# Sheet1.net
KiCad netlist of a schematic drawn in Altium Designer
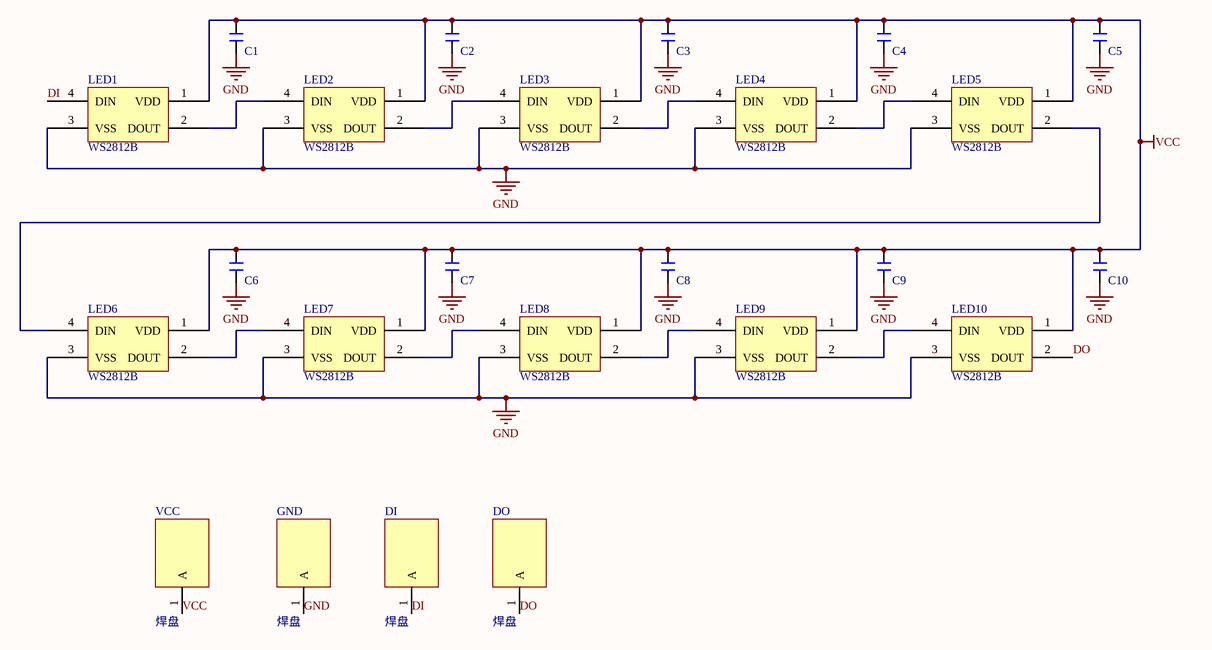
[diagram p0: Sheet1.SchDoc]

(export (version "E")
  (design (tool "Eeschema 10.0.6"))
  (components
    (comp (ref "C1")
      (value "104")
      (footprint "C 0805_M")
      (description "无极性贴片电容")
      (fields (field (name "版权归属") "源创客"))
      (libsource (lib "3.1   - 电阻-电容-电感") (part "C"))
    )
    (comp (ref "C2")
      (value "104")
      (footprint "C 0805_M")
      (description "无极性贴片电容")
      (fields (field (name "版权归属") "源创客"))
      (libsource (lib "3.1   - 电阻-电容-电感") (part "C"))
    )
    (comp (ref "C3")
      (value "104")
      (footprint "C 0805_M")
      (description "无极性贴片电容")
      (fields (field (name "版权归属") "源创客"))
      (libsource (lib "3.1   - 电阻-电容-电感") (part "C"))
    )
    (comp (ref "C4")
      (value "104")
      (footprint "C 0805_M")
      (description "无极性贴片电容")
      (fields (field (name "版权归属") "源创客"))
      (libsource (lib "3.1   - 电阻-电容-电感") (part "C"))
    )
    (comp (ref "C5")
      (value "104")
      (footprint "C 0805_M")
      (description "无极性贴片电容")
      (fields (field (name "版权归属") "源创客"))
      (libsource (lib "3.1   - 电阻-电容-电感") (part "C"))
    )
    (comp (ref "C6")
      (value "104")
      (footprint "C 0805_M")
      (description "无极性贴片电容")
      (fields (field (name "版权归属") "源创客"))
      (libsource (lib "3.1   - 电阻-电容-电感") (part "C"))
    )
    (comp (ref "C7")
      (value "104")
      (footprint "C 0805_M")
      (description "无极性贴片电容")
      (fields (field (name "版权归属") "源创客"))
      (libsource (lib "3.1   - 电阻-电容-电感") (part "C"))
    )
    (comp (ref "C8")
      (value "104")
      (footprint "C 0805_M")
      (description "无极性贴片电容")
      (fields (field (name "版权归属") "源创客"))
      (libsource (lib "3.1   - 电阻-电容-电感") (part "C"))
    )
    (comp (ref "C9")
      (value "104")
      (footprint "C 0805_M")
      (description "无极性贴片电容")
      (fields (field (name "版权归属") "源创客"))
      (libsource (lib "3.1   - 电阻-电容-电感") (part "C"))
    )
    (comp (ref "C10")
      (value "104")
      (footprint "C 0805_M")
      (description "无极性贴片电容")
      (fields (field (name "版权归属") "源创客"))
      (libsource (lib "3.1   - 电阻-电容-电感") (part "C"))
    )
    (comp (ref "DI")
      (value "焊盘")
      (footprint "PCBComponent_1")
      (libsource (lib "8Bit WS2812B RGB Line") (part "焊盘"))
    )
    (comp (ref "DO")
      (value "焊盘")
      (footprint "PCBComponent_1")
      (libsource (lib "8Bit WS2812B RGB Line") (part "焊盘"))
    )
    (comp (ref "GND")
      (value "焊盘")
      (footprint "PCBComponent_1")
      (libsource (lib "8Bit WS2812B RGB Line") (part "焊盘"))
    )
    (comp (ref "LED1")
      (value "WS2812B")
      (footprint "WS2812B")
      (libsource (lib "8Bit WS2812B RGB Line") (part "WS2812B"))
    )
    (comp (ref "LED2")
      (value "WS2812B")
      (footprint "WS2812B")
      (libsource (lib "8Bit WS2812B RGB Line") (part "WS2812B"))
    )
    (comp (ref "LED3")
      (value "WS2812B")
      (footprint "WS2812B")
      (libsource (lib "8Bit WS2812B RGB Line") (part "WS2812B"))
    )
    (comp (ref "LED4")
      (value "WS2812B")
      (footprint "WS2812B")
      (libsource (lib "8Bit WS2812B RGB Line") (part "WS2812B"))
    )
    (comp (ref "LED5")
      (value "WS2812B")
      (footprint "WS2812B")
      (libsource (lib "8Bit WS2812B RGB Line") (part "WS2812B"))
    )
    (comp (ref "LED6")
      (value "WS2812B")
      (footprint "WS2812B")
      (libsource (lib "8Bit WS2812B RGB Line") (part "WS2812B"))
    )
    (comp (ref "LED7")
      (value "WS2812B")
      (footprint "WS2812B")
      (libsource (lib "8Bit WS2812B RGB Line") (part "WS2812B"))
    )
    (comp (ref "LED8")
      (value "WS2812B")
      (footprint "WS2812B")
      (libsource (lib "8Bit WS2812B RGB Line") (part "WS2812B"))
    )
    (comp (ref "LED9")
      (value "WS2812B")
      (footprint "WS2812B")
      (libsource (lib "8Bit WS2812B RGB Line") (part "WS2812B"))
    )
    (comp (ref "LED10")
      (value "WS2812B")
      (footprint "WS2812B")
      (libsource (lib "8Bit WS2812B RGB Line") (part "WS2812B"))
    )
    (comp (ref "VCC")
      (value "焊盘")
      (footprint "PCBComponent_1")
      (libsource (lib "8Bit WS2812B RGB Line") (part "焊盘"))
    )
  )
  (nets
    (net (code "1") (name "/DI") (class "Default")
      (node (ref "DI") (pin "1") (pinfunction "A_1") (pintype "passive"))
      (node (ref "LED1") (pin "4") (pinfunction "DIN_4") (pintype "passive"))
    )
    (net (code "2") (name "/DO") (class "Default")
      (node (ref "DO") (pin "1") (pinfunction "A_1") (pintype "passive"))
      (node (ref "LED10") (pin "2") (pinfunction "DOUT_2") (pintype "passive"))
    )
    (net (code "3") (name "GND") (class "Default")
      (node (ref "C1") (pin "2") (pinfunction "2_2") (pintype "passive"))
      (node (ref "C10") (pin "1") (pinfunction "1_1") (pintype "passive"))
      (node (ref "C2") (pin "2") (pinfunction "2_2") (pintype "passive"))
      (node (ref "C3") (pin "1") (pinfunction "1_1") (pintype "passive"))
      (node (ref "C4") (pin "1") (pinfunction "1_1") (pintype "passive"))
      (node (ref "C5") (pin "2") (pinfunction "2_2") (pintype "passive"))
      (node (ref "C6") (pin "1") (pinfunction "1_1") (pintype "passive"))
      (node (ref "C7") (pin "1") (pinfunction "1_1") (pintype "passive"))
      (node (ref "C8") (pin "2") (pinfunction "2_2") (pintype "passive"))
      (node (ref "C9") (pin "1") (pinfunction "1_1") (pintype "passive"))
      (node (ref "GND") (pin "1") (pinfunction "A_1") (pintype "passive"))
      (node (ref "LED1") (pin "3") (pinfunction "VSS_3") (pintype "passive"))
      (node (ref "LED10") (pin "3") (pinfunction "VSS_3") (pintype "passive"))
      (node (ref "LED2") (pin "3") (pinfunction "VSS_3") (pintype "passive"))
      (node (ref "LED3") (pin "3") (pinfunction "VSS_3") (pintype "passive"))
      (node (ref "LED4") (pin "3") (pinfunction "VSS_3") (pintype "passive"))
      (node (ref "LED5") (pin "3") (pinfunction "VSS_3") (pintype "passive"))
      (node (ref "LED6") (pin "3") (pinfunction "VSS_3") (pintype "passive"))
      (node (ref "LED7") (pin "3") (pinfunction "VSS_3") (pintype "passive"))
      (node (ref "LED8") (pin "3") (pinfunction "VSS_3") (pintype "passive"))
      (node (ref "LED9") (pin "3") (pinfunction "VSS_3") (pintype "passive"))
    )
    (net (code "4") (name "Net-(LED1-DOUT)") (class "Default")
      (node (ref "LED1") (pin "2") (pinfunction "DOUT_2") (pintype "passive"))
      (node (ref "LED2") (pin "4") (pinfunction "DIN_4") (pintype "passive"))
    )
    (net (code "5") (name "Net-(LED2-DOUT)") (class "Default")
      (node (ref "LED2") (pin "2") (pinfunction "DOUT_2") (pintype "passive"))
      (node (ref "LED3") (pin "4") (pinfunction "DIN_4") (pintype "passive"))
    )
    (net (code "6") (name "Net-(LED3-DOUT)") (class "Default")
      (node (ref "LED3") (pin "2") (pinfunction "DOUT_2") (pintype "passive"))
      (node (ref "LED4") (pin "4") (pinfunction "DIN_4") (pintype "passive"))
    )
    (net (code "7") (name "Net-(LED4-DOUT)") (class "Default")
      (node (ref "LED4") (pin "2") (pinfunction "DOUT_2") (pintype "passive"))
      (node (ref "LED5") (pin "4") (pinfunction "DIN_4") (pintype "passive"))
    )
    (net (code "8") (name "Net-(LED5-DOUT)") (class "Default")
      (node (ref "LED5") (pin "2") (pinfunction "DOUT_2") (pintype "passive"))
      (node (ref "LED6") (pin "4") (pinfunction "DIN_4") (pintype "passive"))
    )
    (net (code "9") (name "Net-(LED6-DOUT)") (class "Default")
      (node (ref "LED6") (pin "2") (pinfunction "DOUT_2") (pintype "passive"))
      (node (ref "LED7") (pin "4") (pinfunction "DIN_4") (pintype "passive"))
    )
    (net (code "10") (name "Net-(LED7-DOUT)") (class "Default")
      (node (ref "LED7") (pin "2") (pinfunction "DOUT_2") (pintype "passive"))
      (node (ref "LED8") (pin "4") (pinfunction "DIN_4") (pintype "passive"))
    )
    (net (code "11") (name "Net-(LED8-DOUT)") (class "Default")
      (node (ref "LED8") (pin "2") (pinfunction "DOUT_2") (pintype "passive"))
      (node (ref "LED9") (pin "4") (pinfunction "DIN_4") (pintype "passive"))
    )
    (net (code "12") (name "Net-(LED10-DIN)") (class "Default")
      (node (ref "LED10") (pin "4") (pinfunction "DIN_4") (pintype "passive"))
      (node (ref "LED9") (pin "2") (pinfunction "DOUT_2") (pintype "passive"))
    )
    (net (code "13") (name "VCC") (class "Default")
      (node (ref "C1") (pin "1") (pinfunction "1_1") (pintype "passive"))
      (node (ref "C10") (pin "2") (pinfunction "2_2") (pintype "passive"))
      (node (ref "C2") (pin "1") (pinfunction "1_1") (pintype "passive"))
      (node (ref "C3") (pin "2") (pinfunction "2_2") (pintype "passive"))
      (node (ref "C4") (pin "2") (pinfunction "2_2") (pintype "passive"))
      (node (ref "C5") (pin "1") (pinfunction "1_1") (pintype "passive"))
      (node (ref "C6") (pin "2") (pinfunction "2_2") (pintype "passive"))
      (node (ref "C7") (pin "2") (pinfunction "2_2") (pintype "passive"))
      (node (ref "C8") (pin "1") (pinfunction "1_1") (pintype "passive"))
      (node (ref "C9") (pin "2") (pinfunction "2_2") (pintype "passive"))
      (node (ref "LED1") (pin "1") (pinfunction "VDD_1") (pintype "passive"))
      (node (ref "LED10") (pin "1") (pinfunction "VDD_1") (pintype "passive"))
      (node (ref "LED2") (pin "1") (pinfunction "VDD_1") (pintype "passive"))
      (node (ref "LED3") (pin "1") (pinfunction "VDD_1") (pintype "passive"))
      (node (ref "LED4") (pin "1") (pinfunction "VDD_1") (pintype "passive"))
      (node (ref "LED5") (pin "1") (pinfunction "VDD_1") (pintype "passive"))
      (node (ref "LED6") (pin "1") (pinfunction "VDD_1") (pintype "passive"))
      (node (ref "LED7") (pin "1") (pinfunction "VDD_1") (pintype "passive"))
      (node (ref "LED8") (pin "1") (pinfunction "VDD_1") (pintype "passive"))
      (node (ref "LED9") (pin "1") (pinfunction "VDD_1") (pintype "passive"))
      (node (ref "VCC") (pin "1") (pinfunction "A_1") (pintype "passive"))
    )
  )
)
